# Electronic_load_front_PCB.net
KiCad netlist of a schematic drawn in EAGLE
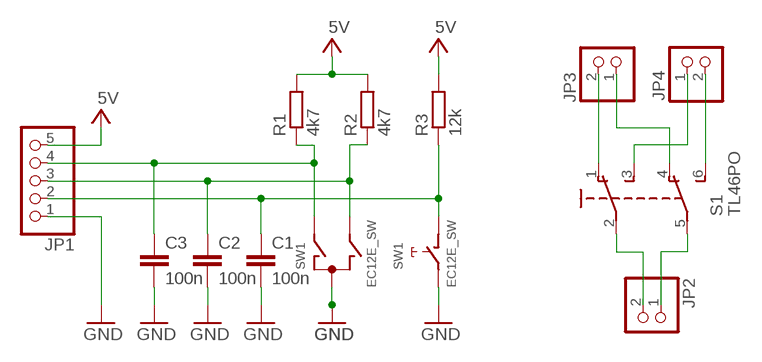
[diagram p0: schematic, sheet 1]

(export (version "E")
  (design (tool "Eeschema 10.0.6"))
  (components
    (comp (ref "C1")
      (value "100n")
      (footprint "eagle-import:C0603")
      (libsource (lib "eagle-import") (part "C-EUC0603"))
    )
    (comp (ref "C2")
      (value "100n")
      (footprint "eagle-import:C0603")
      (libsource (lib "eagle-import") (part "C-EUC0603"))
    )
    (comp (ref "C3")
      (value "100n")
      (footprint "eagle-import:C0603")
      (libsource (lib "eagle-import") (part "C-EUC0603"))
    )
    (comp (ref "JP1")
      (value "PINHD-1X5/90")
      (footprint "eagle-import:1X05_90")
      (libsource (lib "eagle-import") (part "PINHD-1X5/90"))
    )
    (comp (ref "JP2")
      (value "PINHD-1X2/90")
      (footprint "eagle-import:1X02_90")
      (libsource (lib "eagle-import") (part "PINHD-1X2/90"))
    )
    (comp (ref "JP3")
      (value "PINHD-1X2/90")
      (footprint "eagle-import:1X02_90")
      (libsource (lib "eagle-import") (part "PINHD-1X2/90"))
    )
    (comp (ref "JP4")
      (value "PINHD-1X2/90")
      (footprint "eagle-import:1X02_90")
      (libsource (lib "eagle-import") (part "PINHD-1X2/90"))
    )
    (comp (ref "R1")
      (value "4k7")
      (footprint "eagle-import:R0603")
      (libsource (lib "eagle-import") (part "R-EU_R0603"))
    )
    (comp (ref "R2")
      (value "4k7")
      (footprint "eagle-import:R0603")
      (libsource (lib "eagle-import") (part "R-EU_R0603"))
    )
    (comp (ref "R3")
      (value "12k")
      (footprint "eagle-import:R0603")
      (libsource (lib "eagle-import") (part "R-EU_R0603"))
    )
    (comp (ref "S1")
      (value "TL46PO")
      (footprint "eagle-import:TL4XPO")
      (libsource (lib "eagle-import") (part "TL46PO"))
    )
    (comp (ref "SW1")
      (value "EC12E_SW")
      (footprint "eagle-import:ALPS_EC12E_SW")
      (fields (field (name "MPN") "EC12E2424407"))
      (libsource (lib "eagle-import") (part "EC12E_SW"))
    )
  )
  (nets
    (net (code "1") (name "GND") (class "Default")
      (node (ref "C1") (pin "2") (pinfunction "2_2") (pintype "passive"))
      (node (ref "C2") (pin "2") (pinfunction "2_2") (pintype "passive"))
      (node (ref "C3") (pin "2") (pinfunction "2_2") (pintype "passive"))
      (node (ref "JP1") (pin "1") (pinfunction "1_1") (pintype "passive"))
      (node (ref "SW1") (pin "C") (pinfunction "C_C") (pintype "passive"))
      (node (ref "SW1") (pin "E") (pinfunction "2_E") (pintype "passive"))
    )
    (net (code "2") (name "Net-(C2-Pad1)") (class "Default")
      (node (ref "C2") (pin "1") (pinfunction "1_1") (pintype "passive"))
      (node (ref "JP1") (pin "3") (pinfunction "3_3") (pintype "passive"))
      (node (ref "R2") (pin "1") (pinfunction "1_1") (pintype "passive"))
      (node (ref "SW1") (pin "B") (pinfunction "B_B") (pintype "passive"))
    )
    (net (code "3") (name "Net-(C3-Pad1)") (class "Default")
      (node (ref "C3") (pin "1") (pinfunction "1_1") (pintype "passive"))
      (node (ref "JP1") (pin "4") (pinfunction "4_4") (pintype "passive"))
      (node (ref "R1") (pin "1") (pinfunction "1_1") (pintype "passive"))
      (node (ref "SW1") (pin "A") (pinfunction "A_A") (pintype "passive"))
    )
    (net (code "4") (name "Net-(S1-O)") (class "Default")
      (node (ref "JP3") (pin "2") (pinfunction "2_2") (pintype "passive"))
      (node (ref "S1") (pin "1") (pinfunction "O_1") (pintype "passive"))
    )
    (net (code "5") (name "Net-(S1-O1)") (class "Default")
      (node (ref "JP3") (pin "1") (pinfunction "1_1") (pintype "passive"))
      (node (ref "S1") (pin "4") (pinfunction "O1_4") (pintype "passive"))
    )
    (net (code "6") (name "Net-(S1-P)") (class "Default")
      (node (ref "JP2") (pin "2") (pinfunction "2_2") (pintype "passive"))
      (node (ref "S1") (pin "2") (pinfunction "P_2") (pintype "passive"))
    )
    (net (code "7") (name "Net-(S1-P1)") (class "Default")
      (node (ref "JP2") (pin "1") (pinfunction "1_1") (pintype "passive"))
      (node (ref "S1") (pin "5") (pinfunction "P1_5") (pintype "passive"))
    )
    (net (code "8") (name "Net-(S1-S)") (class "Default")
      (node (ref "JP4") (pin "1") (pinfunction "1_1") (pintype "passive"))
      (node (ref "S1") (pin "3") (pinfunction "S_3") (pintype "passive"))
    )
    (net (code "9") (name "Net-(S1-S1)") (class "Default")
      (node (ref "JP4") (pin "2") (pinfunction "2_2") (pintype "passive"))
      (node (ref "S1") (pin "6") (pinfunction "S1_6") (pintype "passive"))
    )
    (net (code "10") (name "Net-(SW1B-1)") (class "Default")
      (node (ref "C1") (pin "1") (pinfunction "1_1") (pintype "passive"))
      (node (ref "JP1") (pin "2") (pinfunction "2_2") (pintype "passive"))
      (node (ref "R3") (pin "1") (pinfunction "1_1") (pintype "passive"))
      (node (ref "SW1") (pin "D") (pinfunction "1_D") (pintype "passive"))
    )
    (net (code "11") (name "VCC") (class "Default")
      (node (ref "JP1") (pin "5") (pinfunction "5_5") (pintype "passive"))
      (node (ref "R1") (pin "2") (pinfunction "2_2") (pintype "passive"))
      (node (ref "R2") (pin "2") (pinfunction "2_2") (pintype "passive"))
      (node (ref "R3") (pin "2") (pinfunction "2_2") (pintype "passive"))
    )
  )
)
